# PX4FLOW2_1_Power_X0.net
KiCad netlist of a schematic drawn in Altium Designer
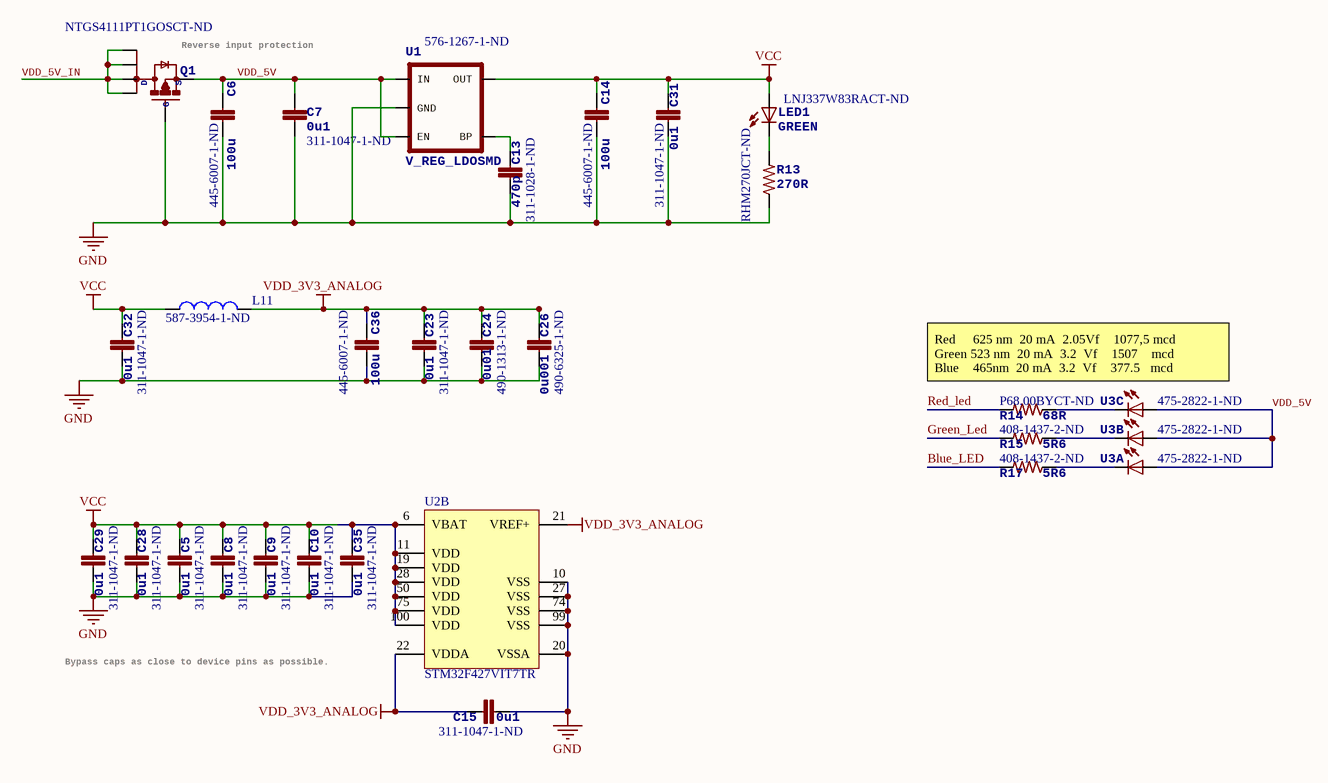
[diagram p0: PX4FLOW2.1_Power_X0.SchDoc]

(export (version "E")
  (design (tool "Eeschema 10.0.6"))
  (components
    (comp (ref "C5")
      (value "0u1")
      (footprint "C0402")
      (description "CapacitorStandard 0603 ceramic capacitor, and 0.1\" leaded capacitor.")
      (fields
        (field (name "PARTNO") "CC0402ZRY5V7BB104")
        (field (name "SUPPLIER PART NUMBER 1") "311-1047-1-ND")
      )
      (libsource (lib "pixhawk2") (part "CAP0402-CAP"))
    )
    (comp (ref "C6")
      (value "100u")
      (footprint "1206-CAP")
      (description "CAP CER 100UF 10V 20% X5R 1206")
      (fields
        (field (name "PARTNO") "C3216X5R1A107M160AC")
        (field (name "SUPPLIER PART NUMBER 1") "445-6007-1-ND")
        (field (name "3DR_PARTNO") "ECM0716")
      )
      (libsource (lib "pixhawk2") (part "CAP1206"))
    )
    (comp (ref "C7")
      (value "0u1")
      (footprint "C0402")
      (description "CapacitorStandard 0603 ceramic capacitor, and 0.1\" leaded capacitor.")
      (fields
        (field (name "PARTNO") "CC0402ZRY5V7BB104")
        (field (name "SUPPLIER PART NUMBER 1") "311-1047-1-ND")
      )
      (libsource (lib "") (part "CAP0402-CAP_2"))
    )
    (comp (ref "C8")
      (value "0u1")
      (footprint "C0402")
      (description "CapacitorStandard 0603 ceramic capacitor, and 0.1\" leaded capacitor.")
      (fields
        (field (name "PARTNO") "CC0402ZRY5V7BB104")
        (field (name "SUPPLIER PART NUMBER 1") "311-1047-1-ND")
      )
      (libsource (lib "pixhawk2") (part "CAP0402-CAP"))
    )
    (comp (ref "C9")
      (value "0u1")
      (footprint "C0402")
      (description "CapacitorStandard 0603 ceramic capacitor, and 0.1\" leaded capacitor.")
      (fields
        (field (name "PARTNO") "CC0402ZRY5V7BB104")
        (field (name "SUPPLIER PART NUMBER 1") "311-1047-1-ND")
      )
      (libsource (lib "pixhawk2") (part "CAP0402-CAP"))
    )
    (comp (ref "C10")
      (value "0u1")
      (footprint "C0402")
      (description "CapacitorStandard 0603 ceramic capacitor, and 0.1\" leaded capacitor.")
      (fields
        (field (name "PARTNO") "CC0402ZRY5V7BB104")
        (field (name "SUPPLIER PART NUMBER 1") "311-1047-1-ND")
      )
      (libsource (lib "pixhawk2") (part "CAP0402-CAP"))
    )
    (comp (ref "C13")
      (value "470p")
      (footprint "C0402")
      (description "CapacitorStandard 0603 ceramic capacitor, and 0.1\" leaded capacitor.")
      (fields
        (field (name "PARTNO") "CC0402KRX7R9BB471")
        (field (name "SUPPLIER PART NUMBER 1") "311-1028-1-ND")
      )
      (libsource (lib "pixhawk2") (part "CAP0402-CAP"))
    )
    (comp (ref "C14")
      (value "100u")
      (footprint "1206-CAP")
      (description "CAP CER 100UF 10V 20% X5R 1206")
      (fields
        (field (name "PARTNO") "C3216X5R1A107M160AC")
        (field (name "SUPPLIER PART NUMBER 1") "445-6007-1-ND")
        (field (name "3DR_PARTNO") "ECM0716")
      )
      (libsource (lib "pixhawk2") (part "CAP1206"))
    )
    (comp (ref "C15")
      (value "0u1")
      (footprint "C0402")
      (description "CapacitorStandard 0603 ceramic capacitor, and 0.1\" leaded capacitor.")
      (fields
        (field (name "PARTNO") "CC0402ZRY5V7BB104")
        (field (name "SUPPLIER PART NUMBER 1") "311-1047-1-ND")
      )
      (libsource (lib "") (part "CAP0402-CAP_1"))
    )
    (comp (ref "C23")
      (value "0u1")
      (footprint "C0402")
      (description "CapacitorStandard 0603 ceramic capacitor, and 0.1\" leaded capacitor.")
      (fields
        (field (name "PARTNO") "CC0402ZRY5V7BB104")
        (field (name "SUPPLIER PART NUMBER 1") "311-1047-1-ND")
      )
      (libsource (lib "pixhawk2") (part "CAP0402-CAP"))
    )
    (comp (ref "C24")
      (value "0u01")
      (footprint "C0402")
      (description "CapacitorStandard 0603 ceramic capacitor, and 0.1\" leaded capacitor.")
      (fields
        (field (name "PARTNO") "CC0402ZRY5V7BB104")
        (field (name "SUPPLIER PART NUMBER 1") "490-1313-1-ND")
      )
      (libsource (lib "pixhawk2") (part "CAP0402-CAP"))
    )
    (comp (ref "C26")
      (value "0u001")
      (footprint "C0402")
      (description "CapacitorStandard 0603 ceramic capacitor, and 0.1\" leaded capacitor.")
      (fields
        (field (name "PARTNO") "CC0402ZRY5V7BB104")
        (field (name "SUPPLIER PART NUMBER 1") "490-6325-1-ND")
      )
      (libsource (lib "pixhawk2") (part "CAP0402-CAP"))
    )
    (comp (ref "C28")
      (value "0u1")
      (footprint "C0402")
      (description "CapacitorStandard 0603 ceramic capacitor, and 0.1\" leaded capacitor.")
      (fields
        (field (name "PARTNO") "CC0402ZRY5V7BB104")
        (field (name "SUPPLIER PART NUMBER 1") "311-1047-1-ND")
      )
      (libsource (lib "pixhawk2") (part "CAP0402-CAP"))
    )
    (comp (ref "C29")
      (value "0u1")
      (footprint "C0402")
      (description "CapacitorStandard 0603 ceramic capacitor, and 0.1\" leaded capacitor.")
      (fields
        (field (name "PARTNO") "CC0402ZRY5V7BB104")
        (field (name "SUPPLIER PART NUMBER 1") "311-1047-1-ND")
      )
      (libsource (lib "pixhawk2") (part "CAP0402-CAP"))
    )
    (comp (ref "C31")
      (value "0u1")
      (footprint "C0402")
      (description "CapacitorStandard 0603 ceramic capacitor, and 0.1\" leaded capacitor.")
      (fields
        (field (name "PARTNO") "CC0402ZRY5V7BB104")
        (field (name "SUPPLIER PART NUMBER 1") "311-1047-1-ND")
      )
      (libsource (lib "pixhawk2") (part "CAP0402-CAP"))
    )
    (comp (ref "C32")
      (value "0u1")
      (footprint "C0402")
      (description "CapacitorStandard 0603 ceramic capacitor, and 0.1\" leaded capacitor.")
      (fields
        (field (name "PARTNO") "CC0402ZRY5V7BB104")
        (field (name "SUPPLIER PART NUMBER 1") "311-1047-1-ND")
      )
      (libsource (lib "pixhawk2") (part "CAP0402-CAP"))
    )
    (comp (ref "C35")
      (value "0u1")
      (footprint "C0402")
      (description "0402")
      (fields
        (field (name "PARTNO") "CC0402ZRY5V7BB104")
        (field (name "SUPPLIER PART NUMBER 1") "311-1047-1-ND")
      )
      (libsource (lib "pixhawk2") (part "CAP0402-CAP"))
    )
    (comp (ref "C36")
      (value "100u")
      (footprint "1206-CAP")
      (description "CAP CER 100UF 10V 20% X5R 1206")
      (fields
        (field (name "PARTNO") "C3216X5R1A107M160AC")
        (field (name "SUPPLIER PART NUMBER 1") "445-6007-1-ND")
        (field (name "3DR_PARTNO") "ECM0716")
      )
      (libsource (lib "pixhawk2") (part "CAP1206"))
    )
    (comp (ref "L11")
      (value "Inductor")
      (footprint "L0402")
      (description "FERRITE BEAD 120 OHM 0402")
      (fields (field (name "SUPPLIER PART NUMBER 1") "587-3954-1-ND"))
      (libsource (lib "3DR") (part "Inductor"))
    )
    (comp (ref "LED1")
      (value "GREEN")
      (footprint "LED-0603")
      (description "Green LED")
      (fields
        (field (name "PARTNO") "LNJ337W83RA")
        (field (name "SUPPLIER PART NUMBER 1") "LNJ337W83RACT-ND")
      )
      (libsource (lib "pixhawk2") (part "LED0603"))
    )
    (comp (ref "Q1")
      (value "NTGS4111P")
      (footprint "TSOP-6")
      (fields
        (field (name "D") "D")
        (field (name "S") "S")
        (field (name "G") "G")
        (field (name "SUPPLIER PART NUMBER 1") "NTGS4111PT1GOSCT-ND")
      )
      (libsource (lib "pixhawk2") (part "NTGS4111P"))
    )
    (comp (ref "R13")
      (value "270R")
      (footprint "R0402")
      (fields (field (name "PARTNO") "MCR01MZPJ271") (field (name "SUPPLIER PART NUMBER 1") "RHM270JCT-ND"))
      (libsource (lib "pixhawk2") (part "RESISTOR0402-RES"))
    )
    (comp (ref "R14")
      (value "68R")
      (footprint "0603-RES")
      (description "RES SMD 68 OHM 1% 1/4W 0603")
      (fields (field (name "PARTNO") "ERJ-PA3F68R0V") (field (name "SUPPLIER PART NUMBER 1") "P68.00BYCT-ND"))
      (libsource (lib "pixhawk2") (part "RESISTOR0402-RES"))
    )
    (comp (ref "R15")
      (value "5R6")
      (footprint "0603-RES")
      (description "RES SMD 5.6 OHM 1% 1/5W 0603")
      (fields (field (name "PARTNO") "RL0816S-5R6-F") (field (name "SUPPLIER PART NUMBER 1") "408-1437-2-ND"))
      (libsource (lib "pixhawk2") (part "RESISTOR0402-RES"))
    )
    (comp (ref "R17")
      (value "5R6")
      (footprint "0603-RES")
      (description "RES SMD 5.6 OHM 1% 1/5W 0603")
      (fields (field (name "PARTNO") "RL0816S-5R6-F") (field (name "SUPPLIER PART NUMBER 1") "408-1437-2-ND"))
      (libsource (lib "pixhawk2") (part "RESISTOR0402-RES"))
    )
    (comp (ref "U1")
      (value "V_REG_LDOSMD")
      (footprint "SOT23-5")
      (fields
        (field (name "PARTNO") "MIC5207-3.3YM5")
        (field (name "SUPPLIER PART NUMBER 1") "576-1267-1-ND")
      )
      (libsource (lib "pixhawk2") (part "V_REG_LDOSMD"))
    )
    (comp (ref "U2")
      (value "STM32F427VIT7TR")
      (footprint "STM-LQFP100_N")
      (fields (field (name "MANUFACTURER") "STMicroelectronics"))
      (libsource (lib "STMicroelectronics STM32 F4") (part "STM32F427VIT7TR"))
    )
    (comp (ref "U3")
      (value "LRTB GFTG-T7AW-1+V7A7-29+R5T9-49-L")
      (footprint "6-PLCC")
      (description "RGB LED with separate anode/cathode terminals")
      (fields (field (name "SUPPLIER PART NUMBER 1") "475-2822-1-ND"))
      (libsource (lib "pixhawk2") (part "RGB-LED6-PLCC"))
    )
  )
  (nets
    (net (code "1") (name "/Blue_LED") (class "Default")
      (node (ref "R17") (pin "2") (pinfunction "2_2") (pintype "passive"))
    )
    (net (code "2") (name "/Green_Led") (class "Default")
      (node (ref "R15") (pin "2") (pinfunction "2_2") (pintype "passive"))
    )
    (net (code "3") (name "/Red_led") (class "Default")
      (node (ref "R14") (pin "2") (pinfunction "2_2") (pintype "passive"))
    )
    (net (code "4") (name "/VDD_5V") (class "Default")
      (node (ref "C6") (pin "P$1") (pinfunction "1_P$1") (pintype "passive"))
      (node (ref "C7") (pin "2") (pinfunction "2_2") (pintype "passive"))
      (node (ref "Q1") (pin "4") (pinfunction "S_4") (pintype "passive"))
      (node (ref "U1") (pin "1") (pinfunction "IN_1") (pintype "passive"))
      (node (ref "U1") (pin "3") (pinfunction "EN_3") (pintype "passive"))
      (node (ref "U3") (pin "A1") (pinfunction "A_A1") (pintype "passive"))
      (node (ref "U3") (pin "A2") (pinfunction "A_A2") (pintype "passive"))
      (node (ref "U3") (pin "A3") (pinfunction "A_A3") (pintype "passive"))
    )
    (net (code "5") (name "/VDD_5V_IN") (class "Default")
      (node (ref "Q1") (pin "1") (pinfunction "D_1") (pintype "passive"))
      (node (ref "Q1") (pin "2") (pinfunction "D1_2") (pintype "passive"))
      (node (ref "Q1") (pin "5") (pinfunction "D2_5") (pintype "passive"))
      (node (ref "Q1") (pin "6") (pinfunction "D3_6") (pintype "passive"))
    )
    (net (code "6") (name "GND") (class "Default")
      (node (ref "C10") (pin "2") (pinfunction "2_2") (pintype "passive"))
      (node (ref "C13") (pin "2") (pinfunction "2_2") (pintype "passive"))
      (node (ref "C14") (pin "P$2") (pinfunction "2_P$2") (pintype "passive"))
      (node (ref "C15") (pin "2") (pinfunction "2_2") (pintype "passive"))
      (node (ref "C23") (pin "2") (pinfunction "2_2") (pintype "passive"))
      (node (ref "C24") (pin "2") (pinfunction "2_2") (pintype "passive"))
      (node (ref "C26") (pin "2") (pinfunction "2_2") (pintype "passive"))
      (node (ref "C28") (pin "2") (pinfunction "2_2") (pintype "passive"))
      (node (ref "C29") (pin "2") (pinfunction "2_2") (pintype "passive"))
      (node (ref "C31") (pin "2") (pinfunction "2_2") (pintype "passive"))
      (node (ref "C32") (pin "2") (pinfunction "2_2") (pintype "passive"))
      (node (ref "C35") (pin "2") (pinfunction "2_2") (pintype "passive"))
      (node (ref "C36") (pin "P$2") (pinfunction "2_P$2") (pintype "passive"))
      (node (ref "C5") (pin "2") (pinfunction "2_2") (pintype "passive"))
      (node (ref "C6") (pin "P$2") (pinfunction "2_P$2") (pintype "passive"))
      (node (ref "C7") (pin "1") (pinfunction "1_1") (pintype "passive"))
      (node (ref "C8") (pin "2") (pinfunction "2_2") (pintype "passive"))
      (node (ref "C9") (pin "2") (pinfunction "2_2") (pintype "passive"))
      (node (ref "Q1") (pin "3") (pinfunction "G_3") (pintype "passive"))
      (node (ref "R13") (pin "1") (pinfunction "1_1") (pintype "passive"))
      (node (ref "U1") (pin "2") (pinfunction "GND_2") (pintype "power_in"))
      (node (ref "U2") (pin "10") (pinfunction "VSS_10") (pintype "power_in"))
      (node (ref "U2") (pin "20") (pinfunction "VSSA_20") (pintype "power_in"))
      (node (ref "U2") (pin "27") (pinfunction "VSS_27") (pintype "power_in"))
      (node (ref "U2") (pin "74") (pinfunction "VSS_74") (pintype "power_in"))
      (node (ref "U2") (pin "99") (pinfunction "VSS_99") (pintype "power_in"))
    )
    (net (code "7") (name "Net-(LED1-PadC)") (class "Default")
      (node (ref "LED1") (pin "C") (pinfunction "C_C") (pintype "passive"))
      (node (ref "R13") (pin "2") (pinfunction "2_2") (pintype "passive"))
    )
    (net (code "8") (name "Net-(U1-BP)") (class "Default")
      (node (ref "C13") (pin "1") (pinfunction "1_1") (pintype "passive"))
      (node (ref "U1") (pin "4") (pinfunction "BP_4") (pintype "passive"))
    )
    (net (code "9") (name "Net-(U3A-C)") (class "Default")
      (node (ref "R17") (pin "1") (pinfunction "1_1") (pintype "passive"))
      (node (ref "U3") (pin "C1") (pinfunction "C_C1") (pintype "passive"))
    )
    (net (code "10") (name "Net-(U3B-C)") (class "Default")
      (node (ref "R15") (pin "1") (pinfunction "1_1") (pintype "passive"))
      (node (ref "U3") (pin "C2") (pinfunction "C_C2") (pintype "passive"))
    )
    (net (code "11") (name "Net-(U3C-C)") (class "Default")
      (node (ref "R14") (pin "1") (pinfunction "1_1") (pintype "passive"))
      (node (ref "U3") (pin "C3") (pinfunction "C_C3") (pintype "passive"))
    )
    (net (code "12") (name "VCC") (class "Default")
      (node (ref "C10") (pin "1") (pinfunction "1_1") (pintype "passive"))
      (node (ref "C14") (pin "P$1") (pinfunction "1_P$1") (pintype "passive"))
      (node (ref "C28") (pin "1") (pinfunction "1_1") (pintype "passive"))
      (node (ref "C29") (pin "1") (pinfunction "1_1") (pintype "passive"))
      (node (ref "C31") (pin "1") (pinfunction "1_1") (pintype "passive"))
      (node (ref "C32") (pin "1") (pinfunction "1_1") (pintype "passive"))
      (node (ref "C35") (pin "1") (pinfunction "1_1") (pintype "passive"))
      (node (ref "C5") (pin "1") (pinfunction "1_1") (pintype "passive"))
      (node (ref "C8") (pin "1") (pinfunction "1_1") (pintype "passive"))
      (node (ref "C9") (pin "1") (pinfunction "1_1") (pintype "passive"))
      (node (ref "L11") (pin "1") (pinfunction "1_1") (pintype "passive"))
      (node (ref "LED1") (pin "A") (pinfunction "A_A") (pintype "passive"))
      (node (ref "U1") (pin "5") (pinfunction "OUT_5") (pintype "passive"))
      (node (ref "U2") (pin "100") (pinfunction "VDD_100") (pintype "power_in"))
      (node (ref "U2") (pin "11") (pinfunction "VDD_11") (pintype "power_in"))
      (node (ref "U2") (pin "19") (pinfunction "VDD_19") (pintype "power_in"))
      (node (ref "U2") (pin "28") (pinfunction "VDD_28") (pintype "power_in"))
      (node (ref "U2") (pin "50") (pinfunction "VDD_50") (pintype "power_in"))
      (node (ref "U2") (pin "6") (pinfunction "VBAT_6") (pintype "power_in"))
      (node (ref "U2") (pin "75") (pinfunction "VDD_75") (pintype "power_in"))
    )
    (net (code "13") (name "VDD_3V3_ANALOG") (class "Default")
      (node (ref "C15") (pin "1") (pinfunction "1_1") (pintype "passive"))
      (node (ref "C23") (pin "1") (pinfunction "1_1") (pintype "passive"))
      (node (ref "C24") (pin "1") (pinfunction "1_1") (pintype "passive"))
      (node (ref "C26") (pin "1") (pinfunction "1_1") (pintype "passive"))
      (node (ref "C36") (pin "P$1") (pinfunction "1_P$1") (pintype "passive"))
      (node (ref "L11") (pin "2") (pinfunction "2_2") (pintype "passive"))
      (node (ref "U2") (pin "21") (pinfunction "VREF+_21") (pintype "power_in"))
      (node (ref "U2") (pin "22") (pinfunction "VDDA_22") (pintype "power_in"))
    )
  )
)
